# R602K.net
KiCad netlist of a schematic drawn in EAGLE
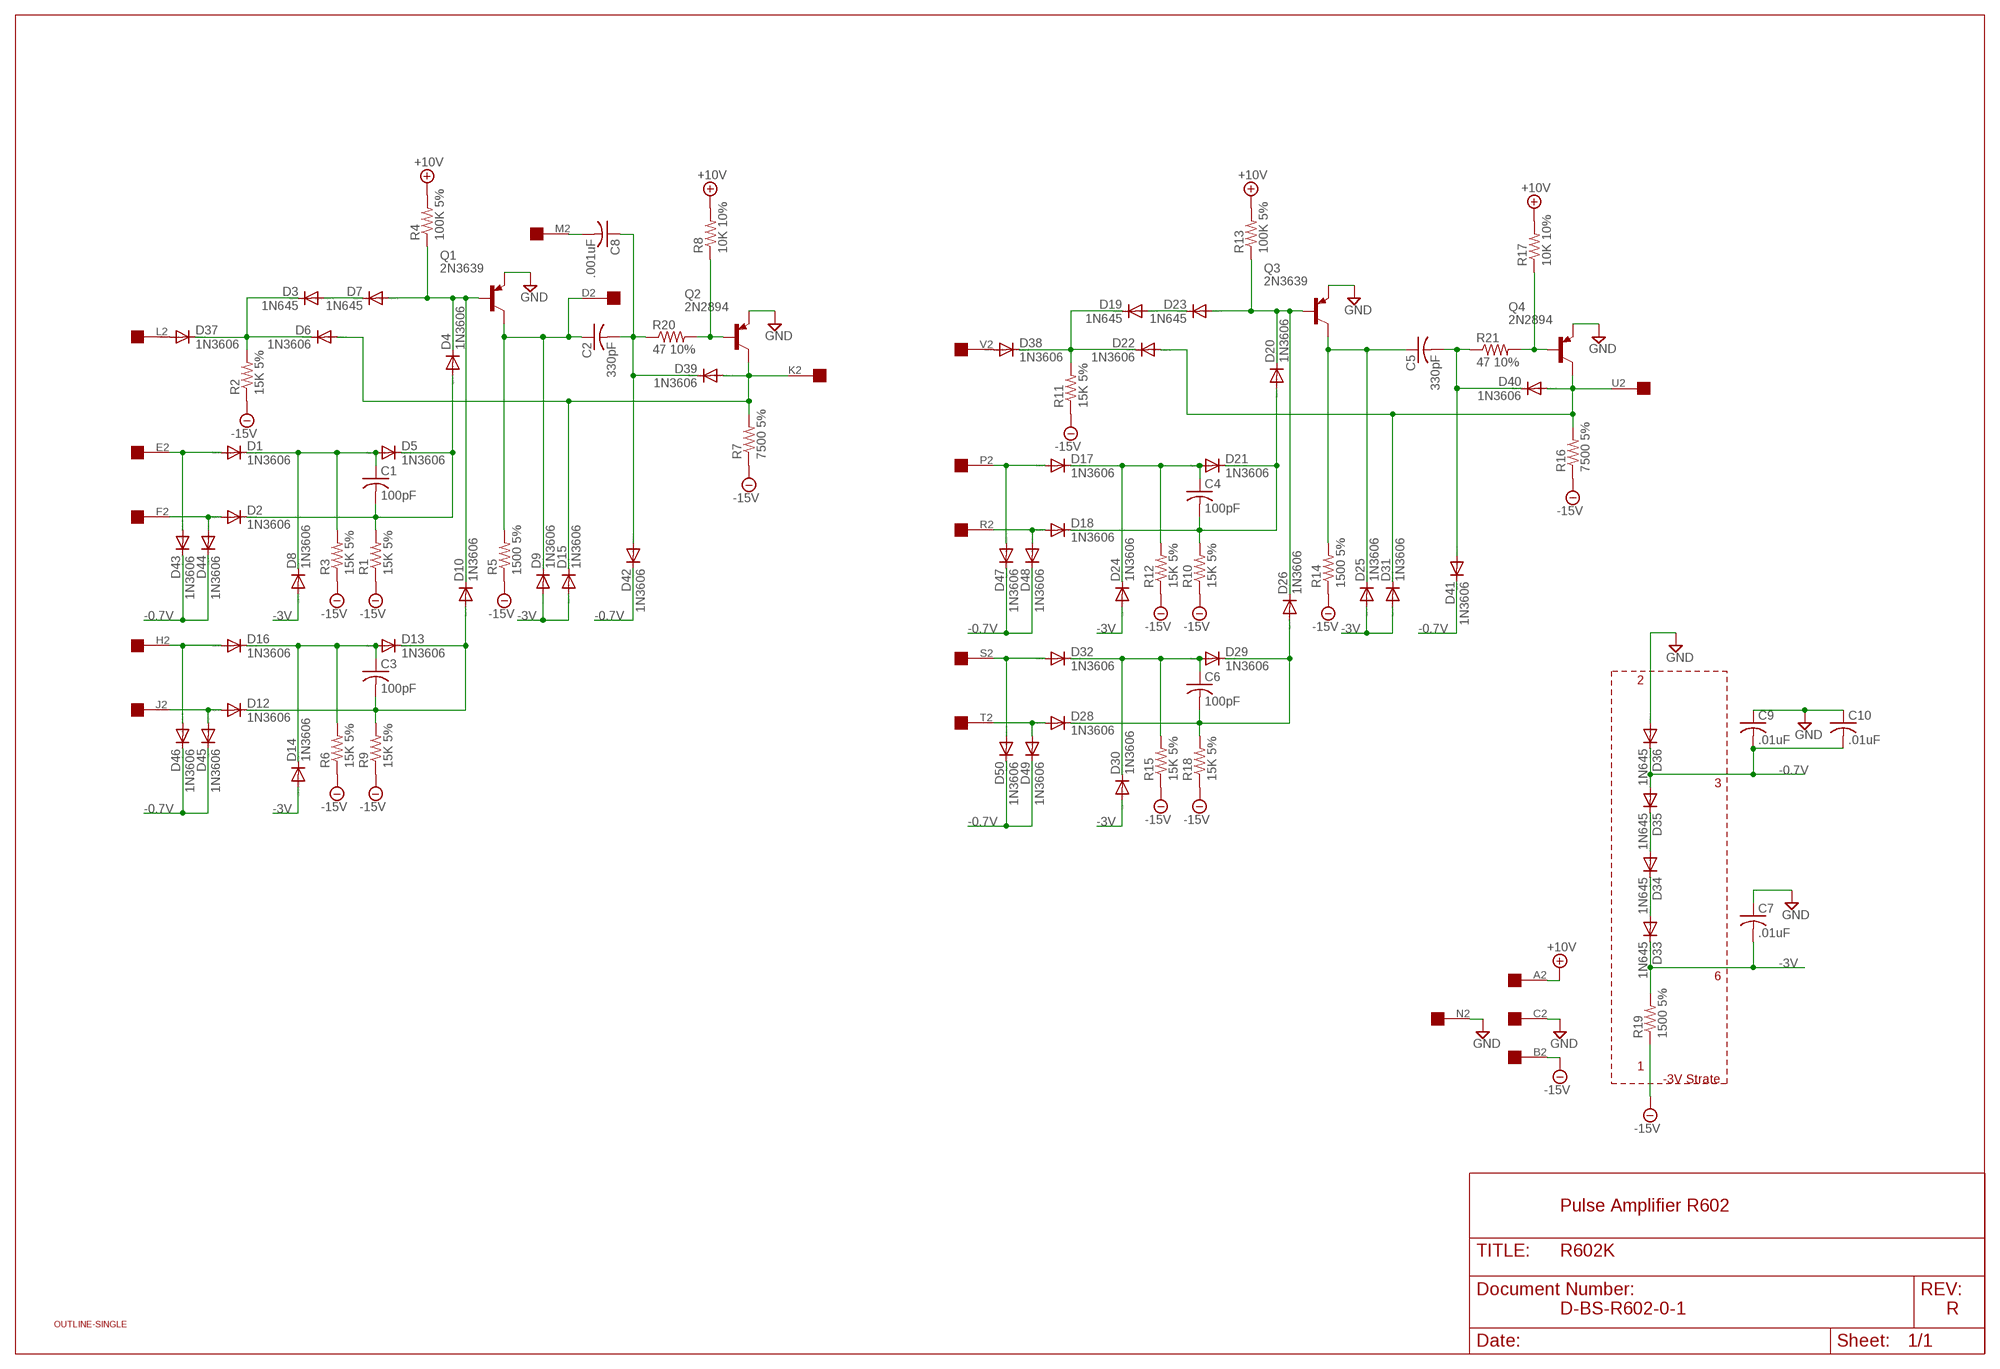
[diagram p0: schematic, sheet 1]

(export (version "E")
  (design (tool "Eeschema 10.0.6"))
  (components
    (comp (ref "C1")
      (value "100pF")
      (footprint "eagle-import:C050-025X075")
      (libsource (lib "eagle-import") (part "C-US050-025X075"))
    )
    (comp (ref "C2")
      (value "330pF")
      (footprint "eagle-import:C050-025X075")
      (libsource (lib "eagle-import") (part "C-US050-025X075"))
    )
    (comp (ref "C3")
      (value "100pF")
      (footprint "eagle-import:C050-025X075")
      (libsource (lib "eagle-import") (part "C-US050-025X075"))
    )
    (comp (ref "C4")
      (value "100pF")
      (footprint "eagle-import:C050-025X075")
      (libsource (lib "eagle-import") (part "C-US050-025X075"))
    )
    (comp (ref "C5")
      (value "330pF")
      (footprint "eagle-import:C050-025X075")
      (libsource (lib "eagle-import") (part "C-US050-025X075"))
    )
    (comp (ref "C6")
      (value "100pF")
      (footprint "eagle-import:C050-025X075")
      (libsource (lib "eagle-import") (part "C-US050-025X075"))
    )
    (comp (ref "C7")
      (value ".01uF")
      (footprint "eagle-import:C075-032X103")
      (libsource (lib "eagle-import") (part "C-US075-032X103"))
    )
    (comp (ref "C8")
      (value ".001uF")
      (footprint "eagle-import:C050-025X075")
      (libsource (lib "eagle-import") (part "C-US050-025X075"))
    )
    (comp (ref "C9")
      (value ".01uF")
      (footprint "eagle-import:C050-025X075")
      (libsource (lib "eagle-import") (part "C-US050-025X075"))
    )
    (comp (ref "C10")
      (value ".01uF")
      (footprint "eagle-import:C050-025X075")
      (libsource (lib "eagle-import") (part "C-US050-025X075"))
    )
    (comp (ref "D1")
      (value "1N3606")
      (footprint "eagle-import:DO35-10")
      (libsource (lib "eagle-import") (part "1N4148DO35-10"))
    )
    (comp (ref "D2")
      (value "1N3606")
      (footprint "eagle-import:DO35-10")
      (libsource (lib "eagle-import") (part "1N4148DO35-10"))
    )
    (comp (ref "D3")
      (value "1N645")
      (footprint "eagle-import:DO35-10")
      (libsource (lib "eagle-import") (part "1N4148DO35-10"))
    )
    (comp (ref "D4")
      (value "1N3606")
      (footprint "eagle-import:DO35-10")
      (libsource (lib "eagle-import") (part "1N4148DO35-10"))
    )
    (comp (ref "D5")
      (value "1N3606")
      (footprint "eagle-import:DO35-10")
      (libsource (lib "eagle-import") (part "1N4148DO35-10"))
    )
    (comp (ref "D6")
      (value "1N3606")
      (footprint "eagle-import:DO35-10")
      (libsource (lib "eagle-import") (part "1N4148DO35-10"))
    )
    (comp (ref "D7")
      (value "1N645")
      (footprint "eagle-import:DO35-10")
      (libsource (lib "eagle-import") (part "1N4148DO35-10"))
    )
    (comp (ref "D8")
      (value "1N3606")
      (footprint "eagle-import:DO35-10")
      (libsource (lib "eagle-import") (part "1N4148DO35-10"))
    )
    (comp (ref "D9")
      (value "1N3606")
      (footprint "eagle-import:DO35-10")
      (libsource (lib "eagle-import") (part "1N4148DO35-10"))
    )
    (comp (ref "D10")
      (value "1N3606")
      (footprint "eagle-import:DO35-10")
      (libsource (lib "eagle-import") (part "1N4148DO35-10"))
    )
    (comp (ref "D12")
      (value "1N3606")
      (footprint "eagle-import:DO35-10")
      (libsource (lib "eagle-import") (part "1N4148DO35-10"))
    )
    (comp (ref "D13")
      (value "1N3606")
      (footprint "eagle-import:DO35-10")
      (libsource (lib "eagle-import") (part "1N4148DO35-10"))
    )
    (comp (ref "D14")
      (value "1N3606")
      (footprint "eagle-import:DO35-10")
      (libsource (lib "eagle-import") (part "1N4148DO35-10"))
    )
    (comp (ref "D15")
      (value "1N3606")
      (footprint "eagle-import:DO35-10")
      (libsource (lib "eagle-import") (part "1N4148DO35-10"))
    )
    (comp (ref "D16")
      (value "1N3606")
      (footprint "eagle-import:DO35-10")
      (libsource (lib "eagle-import") (part "1N4148DO35-10"))
    )
    (comp (ref "D17")
      (value "1N3606")
      (footprint "eagle-import:DO35-10")
      (libsource (lib "eagle-import") (part "1N4148DO35-10"))
    )
    (comp (ref "D18")
      (value "1N3606")
      (footprint "eagle-import:DO35-10")
      (libsource (lib "eagle-import") (part "1N4148DO35-10"))
    )
    (comp (ref "D19")
      (value "1N645")
      (footprint "eagle-import:DO35-10")
      (libsource (lib "eagle-import") (part "1N4148DO35-10"))
    )
    (comp (ref "D20")
      (value "1N3606")
      (footprint "eagle-import:DO35-10")
      (libsource (lib "eagle-import") (part "1N4148DO35-10"))
    )
    (comp (ref "D21")
      (value "1N3606")
      (footprint "eagle-import:DO35-10")
      (libsource (lib "eagle-import") (part "1N4148DO35-10"))
    )
    (comp (ref "D22")
      (value "1N3606")
      (footprint "eagle-import:DO35-10")
      (libsource (lib "eagle-import") (part "1N4148DO35-10"))
    )
    (comp (ref "D23")
      (value "1N645")
      (footprint "eagle-import:DO35-10")
      (libsource (lib "eagle-import") (part "1N4148DO35-10"))
    )
    (comp (ref "D24")
      (value "1N3606")
      (footprint "eagle-import:DO35-10")
      (libsource (lib "eagle-import") (part "1N4148DO35-10"))
    )
    (comp (ref "D25")
      (value "1N3606")
      (footprint "eagle-import:DO35-10")
      (libsource (lib "eagle-import") (part "1N4148DO35-10"))
    )
    (comp (ref "D26")
      (value "1N3606")
      (footprint "eagle-import:DO35-10")
      (libsource (lib "eagle-import") (part "1N4148DO35-10"))
    )
    (comp (ref "D28")
      (value "1N3606")
      (footprint "eagle-import:DO35-10")
      (libsource (lib "eagle-import") (part "1N4148DO35-10"))
    )
    (comp (ref "D29")
      (value "1N3606")
      (footprint "eagle-import:DO35-10")
      (libsource (lib "eagle-import") (part "1N4148DO35-10"))
    )
    (comp (ref "D30")
      (value "1N3606")
      (footprint "eagle-import:DO35-10")
      (libsource (lib "eagle-import") (part "1N4148DO35-10"))
    )
    (comp (ref "D31")
      (value "1N3606")
      (footprint "eagle-import:DO35-10")
      (libsource (lib "eagle-import") (part "1N4148DO35-10"))
    )
    (comp (ref "D32")
      (value "1N3606")
      (footprint "eagle-import:DO35-10")
      (libsource (lib "eagle-import") (part "1N4148DO35-10"))
    )
    (comp (ref "D33")
      (value "1N645")
      (footprint "eagle-import:DO35-10")
      (libsource (lib "eagle-import") (part "1N4148DO35-10"))
    )
    (comp (ref "D34")
      (value "1N645")
      (footprint "eagle-import:DO35-10")
      (libsource (lib "eagle-import") (part "1N4148DO35-10"))
    )
    (comp (ref "D35")
      (value "1N645")
      (footprint "eagle-import:DO35-10")
      (libsource (lib "eagle-import") (part "1N4148DO35-10"))
    )
    (comp (ref "D36")
      (value "1N645")
      (footprint "eagle-import:DO35-10")
      (libsource (lib "eagle-import") (part "1N4148DO35-10"))
    )
    (comp (ref "D37")
      (value "1N3606")
      (footprint "eagle-import:DO35-10")
      (libsource (lib "eagle-import") (part "1N4148DO35-10"))
    )
    (comp (ref "D38")
      (value "1N3606")
      (footprint "eagle-import:DO35-10")
      (libsource (lib "eagle-import") (part "1N4148DO35-10"))
    )
    (comp (ref "D39")
      (value "1N3606")
      (footprint "eagle-import:DO35-10")
      (libsource (lib "eagle-import") (part "1N4148DO35-10"))
    )
    (comp (ref "D40")
      (value "1N3606")
      (footprint "eagle-import:DO35-10")
      (libsource (lib "eagle-import") (part "1N4148DO35-10"))
    )
    (comp (ref "D41")
      (value "1N3606")
      (footprint "eagle-import:DO35-10")
      (libsource (lib "eagle-import") (part "1N4148DO35-10"))
    )
    (comp (ref "D42")
      (value "1N3606")
      (footprint "eagle-import:DO35-10")
      (libsource (lib "eagle-import") (part "1N4148DO35-10"))
    )
    (comp (ref "D43")
      (value "1N3606")
      (footprint "eagle-import:DO35-10")
      (libsource (lib "eagle-import") (part "1N4148DO35-10"))
    )
    (comp (ref "D44")
      (value "1N3606")
      (footprint "eagle-import:DO35-10")
      (libsource (lib "eagle-import") (part "1N4148DO35-10"))
    )
    (comp (ref "D45")
      (value "1N3606")
      (footprint "eagle-import:DO35-10")
      (libsource (lib "eagle-import") (part "1N4148DO35-10"))
    )
    (comp (ref "D46")
      (value "1N3606")
      (footprint "eagle-import:DO35-10")
      (libsource (lib "eagle-import") (part "1N4148DO35-10"))
    )
    (comp (ref "D47")
      (value "1N3606")
      (footprint "eagle-import:DO35-10")
      (libsource (lib "eagle-import") (part "1N4148DO35-10"))
    )
    (comp (ref "D48")
      (value "1N3606")
      (footprint "eagle-import:DO35-10")
      (libsource (lib "eagle-import") (part "1N4148DO35-10"))
    )
    (comp (ref "D49")
      (value "1N3606")
      (footprint "eagle-import:DO35-10")
      (libsource (lib "eagle-import") (part "1N4148DO35-10"))
    )
    (comp (ref "D50")
      (value "1N3606")
      (footprint "eagle-import:DO35-10")
      (libsource (lib "eagle-import") (part "1N4148DO35-10"))
    )
    (comp (ref "Q1")
      (value "2N3639")
      (footprint "eagle-import:TO39")
      (libsource (lib "eagle-import") (part "2N2904"))
    )
    (comp (ref "Q2")
      (value "2N2894")
      (footprint "eagle-import:TO39")
      (libsource (lib "eagle-import") (part "2N2904"))
    )
    (comp (ref "Q3")
      (value "2N3639")
      (footprint "eagle-import:TO39")
      (libsource (lib "eagle-import") (part "2N2904"))
    )
    (comp (ref "Q4")
      (value "2N2894")
      (footprint "eagle-import:TO39")
      (libsource (lib "eagle-import") (part "2N2904"))
    )
    (comp (ref "R1")
      (value "15K 5%")
      (footprint "eagle-import:0207_10")
      (libsource (lib "eagle-import") (part "R-US_0207/10"))
    )
    (comp (ref "R2")
      (value "15K 5%")
      (footprint "eagle-import:0207_10")
      (libsource (lib "eagle-import") (part "R-US_0207/10"))
    )
    (comp (ref "R3")
      (value "15K 5%")
      (footprint "eagle-import:0207_10")
      (libsource (lib "eagle-import") (part "R-US_0207/10"))
    )
    (comp (ref "R4")
      (value "100K 5%")
      (footprint "eagle-import:0207_10")
      (libsource (lib "eagle-import") (part "R-US_0207/10"))
    )
    (comp (ref "R5")
      (value "1500 5%")
      (footprint "eagle-import:0207_10")
      (libsource (lib "eagle-import") (part "R-US_0207/10"))
    )
    (comp (ref "R6")
      (value "15K 5%")
      (footprint "eagle-import:0207_10")
      (libsource (lib "eagle-import") (part "R-US_0207/10"))
    )
    (comp (ref "R7")
      (value "7500 5%")
      (footprint "eagle-import:0207_10")
      (libsource (lib "eagle-import") (part "R-US_0207/10"))
    )
    (comp (ref "R8")
      (value "10K 10%")
      (footprint "eagle-import:0207_10")
      (libsource (lib "eagle-import") (part "R-US_0207/10"))
    )
    (comp (ref "R9")
      (value "15K 5%")
      (footprint "eagle-import:0207_10")
      (libsource (lib "eagle-import") (part "R-US_0207/10"))
    )
    (comp (ref "R10")
      (value "15K 5%")
      (footprint "eagle-import:0207_10")
      (libsource (lib "eagle-import") (part "R-US_0207/10"))
    )
    (comp (ref "R11")
      (value "15K 5%")
      (footprint "eagle-import:0207_10")
      (libsource (lib "eagle-import") (part "R-US_0207/10"))
    )
    (comp (ref "R12")
      (value "15K 5%")
      (footprint "eagle-import:0207_10")
      (libsource (lib "eagle-import") (part "R-US_0207/10"))
    )
    (comp (ref "R13")
      (value "100K 5%")
      (footprint "eagle-import:0207_10")
      (libsource (lib "eagle-import") (part "R-US_0207/10"))
    )
    (comp (ref "R14")
      (value "1500 5%")
      (footprint "eagle-import:0207_10")
      (libsource (lib "eagle-import") (part "R-US_0207/10"))
    )
    (comp (ref "R15")
      (value "15K 5%")
      (footprint "eagle-import:0207_10")
      (libsource (lib "eagle-import") (part "R-US_0207/10"))
    )
    (comp (ref "R16")
      (value "7500 5%")
      (footprint "eagle-import:0207_10")
      (libsource (lib "eagle-import") (part "R-US_0207/10"))
    )
    (comp (ref "R17")
      (value "10K 10%")
      (footprint "eagle-import:0207_10")
      (libsource (lib "eagle-import") (part "R-US_0207/10"))
    )
    (comp (ref "R18")
      (value "15K 5%")
      (footprint "eagle-import:0207_10")
      (libsource (lib "eagle-import") (part "R-US_0207/10"))
    )
    (comp (ref "R19")
      (value "1500 5%")
      (footprint "eagle-import:0207_10")
      (libsource (lib "eagle-import") (part "R-US_0207/10"))
    )
    (comp (ref "R20")
      (value "47 10%")
      (footprint "eagle-import:0207_10")
      (libsource (lib "eagle-import") (part "R-US_0207/10"))
    )
    (comp (ref "R21")
      (value "47 10%")
      (footprint "eagle-import:0207_10")
      (libsource (lib "eagle-import") (part "R-US_0207/10"))
    )
    (comp (ref "U$1")
      (value "OUTLINE-SINGLE")
      (footprint "eagle-import:SINGLE")
      (libsource (lib "eagle-import") (part "OUTLINE-SINGLE"))
    )
    (comp (ref "U$2")
      (value "EDGE-1")
      (footprint "eagle-import:EDGE-CON1")
      (libsource (lib "eagle-import") (part "EDGE-1"))
    )
  )
  (nets
    (net (code "1") (name "+10V") (class "Default")
      (node (ref "R13") (pin "2") (pinfunction "2_2") (pintype "passive"))
      (node (ref "R17") (pin "2") (pinfunction "2_2") (pintype "passive"))
      (node (ref "R4") (pin "2") (pinfunction "2_2") (pintype "passive"))
      (node (ref "R8") (pin "2") (pinfunction "2_2") (pintype "passive"))
      (node (ref "U$2") (pin "A2") (pinfunction "1_A2") (pintype "bidirectional"))
    )
    (net (code "2") (name "-15V") (class "Default")
      (node (ref "R1") (pin "1") (pinfunction "1_1") (pintype "passive"))
      (node (ref "R10") (pin "1") (pinfunction "1_1") (pintype "passive"))
      (node (ref "R11") (pin "1") (pinfunction "1_1") (pintype "passive"))
      (node (ref "R12") (pin "1") (pinfunction "1_1") (pintype "passive"))
      (node (ref "R14") (pin "1") (pinfunction "1_1") (pintype "passive"))
      (node (ref "R15") (pin "1") (pinfunction "1_1") (pintype "passive"))
      (node (ref "R16") (pin "1") (pinfunction "1_1") (pintype "passive"))
      (node (ref "R18") (pin "1") (pinfunction "1_1") (pintype "passive"))
      (node (ref "R19") (pin "1") (pinfunction "1_1") (pintype "passive"))
      (node (ref "R2") (pin "1") (pinfunction "1_1") (pintype "passive"))
      (node (ref "R3") (pin "1") (pinfunction "1_1") (pintype "passive"))
      (node (ref "R5") (pin "1") (pinfunction "1_1") (pintype "passive"))
      (node (ref "R6") (pin "1") (pinfunction "1_1") (pintype "passive"))
      (node (ref "R7") (pin "1") (pinfunction "1_1") (pintype "passive"))
      (node (ref "R9") (pin "1") (pinfunction "1_1") (pintype "passive"))
      (node (ref "U$2") (pin "B2") (pinfunction "1_B2") (pintype "bidirectional"))
    )
    (net (code "3") (name "/-0.7V") (class "Default")
      (node (ref "C10") (pin "2") (pinfunction "2_2") (pintype "passive"))
      (node (ref "C9") (pin "2") (pinfunction "2_2") (pintype "passive"))
      (node (ref "D35") (pin "A") (pinfunction "A_A") (pintype "passive"))
      (node (ref "D36") (pin "C") (pinfunction "C_C") (pintype "passive"))
      (node (ref "D41") (pin "C") (pinfunction "C_C") (pintype "passive"))
      (node (ref "D42") (pin "C") (pinfunction "C_C") (pintype "passive"))
      (node (ref "D43") (pin "C") (pinfunction "C_C") (pintype "passive"))
      (node (ref "D44") (pin "C") (pinfunction "C_C") (pintype "passive"))
      (node (ref "D45") (pin "C") (pinfunction "C_C") (pintype "passive"))
      (node (ref "D46") (pin "C") (pinfunction "C_C") (pintype "passive"))
      (node (ref "D47") (pin "C") (pinfunction "C_C") (pintype "passive"))
      (node (ref "D48") (pin "C") (pinfunction "C_C") (pintype "passive"))
      (node (ref "D49") (pin "C") (pinfunction "C_C") (pintype "passive"))
      (node (ref "D50") (pin "C") (pinfunction "C_C") (pintype "passive"))
    )
    (net (code "4") (name "/-3V") (class "Default")
      (node (ref "C7") (pin "2") (pinfunction "2_2") (pintype "passive"))
      (node (ref "D14") (pin "A") (pinfunction "A_A") (pintype "passive"))
      (node (ref "D15") (pin "A") (pinfunction "A_A") (pintype "passive"))
      (node (ref "D24") (pin "A") (pinfunction "A_A") (pintype "passive"))
      (node (ref "D25") (pin "A") (pinfunction "A_A") (pintype "passive"))
      (node (ref "D30") (pin "A") (pinfunction "A_A") (pintype "passive"))
      (node (ref "D31") (pin "A") (pinfunction "A_A") (pintype "passive"))
      (node (ref "D33") (pin "C") (pinfunction "C_C") (pintype "passive"))
      (node (ref "D8") (pin "A") (pinfunction "A_A") (pintype "passive"))
      (node (ref "D9") (pin "A") (pinfunction "A_A") (pintype "passive"))
      (node (ref "R19") (pin "2") (pinfunction "2_2") (pintype "passive"))
    )
    (net (code "5") (name "GND") (class "Default")
      (node (ref "C10") (pin "1") (pinfunction "1_1") (pintype "passive"))
      (node (ref "C7") (pin "1") (pinfunction "1_1") (pintype "passive"))
      (node (ref "C9") (pin "1") (pinfunction "1_1") (pintype "passive"))
      (node (ref "D36") (pin "A") (pinfunction "A_A") (pintype "passive"))
      (node (ref "Q1") (pin "1") (pinfunction "E_1") (pintype "passive"))
      (node (ref "Q2") (pin "1") (pinfunction "E_1") (pintype "passive"))
      (node (ref "Q3") (pin "1") (pinfunction "E_1") (pintype "passive"))
      (node (ref "Q4") (pin "1") (pinfunction "E_1") (pintype "passive"))
      (node (ref "U$2") (pin "C2") (pinfunction "1_C2") (pintype "bidirectional"))
      (node (ref "U$2") (pin "N2") (pinfunction "1_N2") (pintype "bidirectional"))
    )
    (net (code "6") (name "Net-(C1-Pad1)") (class "Default")
      (node (ref "C1") (pin "1") (pinfunction "1_1") (pintype "passive"))
      (node (ref "D1") (pin "C") (pinfunction "C_C") (pintype "passive"))
      (node (ref "D5") (pin "A") (pinfunction "A_A") (pintype "passive"))
      (node (ref "D8") (pin "C") (pinfunction "C_C") (pintype "passive"))
      (node (ref "R3") (pin "2") (pinfunction "2_2") (pintype "passive"))
    )
    (net (code "7") (name "Net-(C1-Pad2)") (class "Default")
      (node (ref "C1") (pin "2") (pinfunction "2_2") (pintype "passive"))
      (node (ref "D2") (pin "C") (pinfunction "C_C") (pintype "passive"))
      (node (ref "D4") (pin "A") (pinfunction "A_A") (pintype "passive"))
      (node (ref "D5") (pin "C") (pinfunction "C_C") (pintype "passive"))
      (node (ref "R1") (pin "2") (pinfunction "2_2") (pintype "passive"))
    )
    (net (code "8") (name "Net-(C2-Pad2)") (class "Default")
      (node (ref "C2") (pin "2") (pinfunction "2_2") (pintype "passive"))
      (node (ref "C8") (pin "1") (pinfunction "1_1") (pintype "passive"))
      (node (ref "D39") (pin "C") (pinfunction "C_C") (pintype "passive"))
      (node (ref "D42") (pin "A") (pinfunction "A_A") (pintype "passive"))
      (node (ref "R20") (pin "1") (pinfunction "1_1") (pintype "passive"))
    )
    (net (code "9") (name "Net-(C3-Pad1)") (class "Default")
      (node (ref "C3") (pin "1") (pinfunction "1_1") (pintype "passive"))
      (node (ref "D13") (pin "A") (pinfunction "A_A") (pintype "passive"))
      (node (ref "D14") (pin "C") (pinfunction "C_C") (pintype "passive"))
      (node (ref "D16") (pin "C") (pinfunction "C_C") (pintype "passive"))
      (node (ref "R6") (pin "2") (pinfunction "2_2") (pintype "passive"))
    )
    (net (code "10") (name "Net-(C3-Pad2)") (class "Default")
      (node (ref "C3") (pin "2") (pinfunction "2_2") (pintype "passive"))
      (node (ref "D10") (pin "A") (pinfunction "A_A") (pintype "passive"))
      (node (ref "D12") (pin "C") (pinfunction "C_C") (pintype "passive"))
      (node (ref "D13") (pin "C") (pinfunction "C_C") (pintype "passive"))
      (node (ref "R9") (pin "2") (pinfunction "2_2") (pintype "passive"))
    )
    (net (code "11") (name "Net-(C4-Pad1)") (class "Default")
      (node (ref "C4") (pin "1") (pinfunction "1_1") (pintype "passive"))
      (node (ref "D17") (pin "C") (pinfunction "C_C") (pintype "passive"))
      (node (ref "D21") (pin "A") (pinfunction "A_A") (pintype "passive"))
      (node (ref "D24") (pin "C") (pinfunction "C_C") (pintype "passive"))
      (node (ref "R12") (pin "2") (pinfunction "2_2") (pintype "passive"))
    )
    (net (code "12") (name "Net-(C4-Pad2)") (class "Default")
      (node (ref "C4") (pin "2") (pinfunction "2_2") (pintype "passive"))
      (node (ref "D18") (pin "C") (pinfunction "C_C") (pintype "passive"))
      (node (ref "D20") (pin "A") (pinfunction "A_A") (pintype "passive"))
      (node (ref "D21") (pin "C") (pinfunction "C_C") (pintype "passive"))
      (node (ref "R10") (pin "2") (pinfunction "2_2") (pintype "passive"))
    )
    (net (code "13") (name "Net-(C5-Pad2)") (class "Default")
      (node (ref "C5") (pin "2") (pinfunction "2_2") (pintype "passive"))
      (node (ref "D40") (pin "C") (pinfunction "C_C") (pintype "passive"))
      (node (ref "D41") (pin "A") (pinfunction "A_A") (pintype "passive"))
      (node (ref "R21") (pin "1") (pinfunction "1_1") (pintype "passive"))
    )
    (net (code "14") (name "Net-(C6-Pad1)") (class "Default")
      (node (ref "C6") (pin "1") (pinfunction "1_1") (pintype "passive"))
      (node (ref "D29") (pin "A") (pinfunction "A_A") (pintype "passive"))
      (node (ref "D30") (pin "C") (pinfunction "C_C") (pintype "passive"))
      (node (ref "D32") (pin "C") (pinfunction "C_C") (pintype "passive"))
      (node (ref "R15") (pin "2") (pinfunction "2_2") (pintype "passive"))
    )
    (net (code "15") (name "Net-(C6-Pad2)") (class "Default")
      (node (ref "C6") (pin "2") (pinfunction "2_2") (pintype "passive"))
      (node (ref "D26") (pin "A") (pinfunction "A_A") (pintype "passive"))
      (node (ref "D28") (pin "C") (pinfunction "C_C") (pintype "passive"))
      (node (ref "D29") (pin "C") (pinfunction "C_C") (pintype "passive"))
      (node (ref "R18") (pin "2") (pinfunction "2_2") (pintype "passive"))
    )
    (net (code "16") (name "Net-(D3-PadA)") (class "Default")
      (node (ref "D3") (pin "A") (pinfunction "A_A") (pintype "passive"))
      (node (ref "D7") (pin "C") (pinfunction "C_C") (pintype "passive"))
    )
    (net (code "17") (name "Net-(D3-PadC)") (class "Default")
      (node (ref "D3") (pin "C") (pinfunction "C_C") (pintype "passive"))
      (node (ref "D37") (pin "C") (pinfunction "C_C") (pintype "passive"))
      (node (ref "D6") (pin "C") (pinfunction "C_C") (pintype "passive"))
      (node (ref "R2") (pin "2") (pinfunction "2_2") (pintype "passive"))
    )
    (net (code "18") (name "Net-(D19-PadA)") (class "Default")
      (node (ref "D19") (pin "A") (pinfunction "A_A") (pintype "passive"))
      (node (ref "D23") (pin "C") (pinfunction "C_C") (pintype "passive"))
    )
    (net (code "19") (name "Net-(D19-PadC)") (class "Default")
      (node (ref "D19") (pin "C") (pinfunction "C_C") (pintype "passive"))
      (node (ref "D22") (pin "C") (pinfunction "C_C") (pintype "passive"))
      (node (ref "D38") (pin "C") (pinfunction "C_C") (pintype "passive"))
      (node (ref "R11") (pin "2") (pinfunction "2_2") (pintype "passive"))
    )
    (net (code "20") (name "Net-(D33-PadA)") (class "Default")
      (node (ref "D33") (pin "A") (pinfunction "A_A") (pintype "passive"))
      (node (ref "D34") (pin "C") (pinfunction "C_C") (pintype "passive"))
    )
    (net (code "21") (name "Net-(D34-PadA)") (class "Default")
      (node (ref "D34") (pin "A") (pinfunction "A_A") (pintype "passive"))
      (node (ref "D35") (pin "C") (pinfunction "C_C") (pintype "passive"))
    )
    (net (code "22") (name "Net-(Q1-B)") (class "Default")
      (node (ref "D10") (pin "C") (pinfunction "C_C") (pintype "passive"))
      (node (ref "D4") (pin "C") (pinfunction "C_C") (pintype "passive"))
      (node (ref "D7") (pin "A") (pinfunction "A_A") (pintype "passive"))
      (node (ref "Q1") (pin "2") (pinfunction "B_2") (pintype "passive"))
      (node (ref "R4") (pin "1") (pinfunction "1_1") (pintype "passive"))
    )
    (net (code "23") (name "Net-(Q1-C)") (class "Default")
      (node (ref "C2") (pin "1") (pinfunction "1_1") (pintype "passive"))
      (node (ref "D9") (pin "C") (pinfunction "C_C") (pintype "passive"))
      (node (ref "Q1") (pin "3") (pinfunction "C_3") (pintype "passive"))
      (node (ref "R5") (pin "2") (pinfunction "2_2") (pintype "passive"))
      (node (ref "U$2") (pin "D2") (pinfunction "1_D2") (pintype "bidirectional"))
    )
    (net (code "24") (name "Net-(Q2-B)") (class "Default")
      (node (ref "Q2") (pin "2") (pinfunction "B_2") (pintype "passive"))
      (node (ref "R20") (pin "2") (pinfunction "2_2") (pintype "passive"))
      (node (ref "R8") (pin "1") (pinfunction "1_1") (pintype "passive"))
    )
    (net (code "25") (name "Net-(Q2-C)") (class "Default")
      (node (ref "D15") (pin "C") (pinfunction "C_C") (pintype "passive"))
      (node (ref "D39") (pin "A") (pinfunction "A_A") (pintype "passive"))
      (node (ref "D6") (pin "A") (pinfunction "A_A") (pintype "passive"))
      (node (ref "Q2") (pin "3") (pinfunction "C_3") (pintype "passive"))
      (node (ref "R7") (pin "2") (pinfunction "2_2") (pintype "passive"))
      (node (ref "U$2") (pin "K2") (pinfunction "1_K2") (pintype "bidirectional"))
    )
    (net (code "26") (name "Net-(Q3-B)") (class "Default")
      (node (ref "D20") (pin "C") (pinfunction "C_C") (pintype "passive"))
      (node (ref "D23") (pin "A") (pinfunction "A_A") (pintype "passive"))
      (node (ref "D26") (pin "C") (pinfunction "C_C") (pintype "passive"))
      (node (ref "Q3") (pin "2") (pinfunction "B_2") (pintype "passive"))
      (node (ref "R13") (pin "1") (pinfunction "1_1") (pintype "passive"))
    )
    (net (code "27") (name "Net-(Q3-C)") (class "Default")
      (node (ref "C5") (pin "1") (pinfunction "1_1") (pintype "passive"))
      (node (ref "D25") (pin "C") (pinfunction "C_C") (pintype "passive"))
      (node (ref "Q3") (pin "3") (pinfunction "C_3") (pintype "passive"))
      (node (ref "R14") (pin "2") (pinfunction "2_2") (pintype "passive"))
    )
    (net (code "28") (name "Net-(Q4-B)") (class "Default")
      (node (ref "Q4") (pin "2") (pinfunction "B_2") (pintype "passive"))
      (node (ref "R17") (pin "1") (pinfunction "1_1") (pintype "passive"))
      (node (ref "R21") (pin "2") (pinfunction "2_2") (pintype "passive"))
    )
    (net (code "29") (name "Net-(Q4-C)") (class "Default")
      (node (ref "D22") (pin "A") (pinfunction "A_A") (pintype "passive"))
      (node (ref "D31") (pin "C") (pinfunction "C_C") (pintype "passive"))
      (node (ref "D40") (pin "A") (pinfunction "A_A") (pintype "passive"))
      (node (ref "Q4") (pin "3") (pinfunction "C_3") (pintype "passive"))
      (node (ref "R16") (pin "2") (pinfunction "2_2") (pintype "passive"))
      (node (ref "U$2") (pin "U2") (pinfunction "1_U2") (pintype "bidirectional"))
    )
    (net (code "30") (name "Net-(U$2E-1)") (class "Default")
      (node (ref "D1") (pin "A") (pinfunction "A_A") (pintype "passive"))
      (node (ref "D43") (pin "A") (pinfunction "A_A") (pintype "passive"))
      (node (ref "U$2") (pin "E2") (pinfunction "1_E2") (pintype "bidirectional"))
    )
    (net (code "31") (name "Net-(U$2F-1)") (class "Default")
      (node (ref "D2") (pin "A") (pinfunction "A_A") (pintype "passive"))
      (node (ref "D44") (pin "A") (pinfunction "A_A") (pintype "passive"))
      (node (ref "U$2") (pin "F2") (pinfunction "1_F2") (pintype "bidirectional"))
    )
    (net (code "32") (name "Net-(U$2G-1)") (class "Default")
      (node (ref "D16") (pin "A") (pinfunction "A_A") (pintype "passive"))
      (node (ref "D46") (pin "A") (pinfunction "A_A") (pintype "passive"))
      (node (ref "U$2") (pin "H2") (pinfunction "1_H2") (pintype "bidirectional"))
    )
    (net (code "33") (name "Net-(U$2H-1)") (class "Default")
      (node (ref "D12") (pin "A") (pinfunction "A_A") (pintype "passive"))
      (node (ref "D45") (pin "A") (pinfunction "A_A") (pintype "passive"))
      (node (ref "U$2") (pin "J2") (pinfunction "1_J2") (pintype "bidirectional"))
    )
    (net (code "34") (name "Net-(U$2J-1)") (class "Default")
      (node (ref "D37") (pin "A") (pinfunction "A_A") (pintype "passive"))
      (node (ref "U$2") (pin "L2") (pinfunction "1_L2") (pintype "bidirectional"))
    )
    (net (code "35") (name "Net-(U$2K-1)") (class "Default")
      (node (ref "C8") (pin "2") (pinfunction "2_2") (pintype "passive"))
      (node (ref "U$2") (pin "M2") (pinfunction "1_M2") (pintype "bidirectional"))
    )
    (net (code "36") (name "Net-(U$2M-1)") (class "Default")
      (node (ref "D17") (pin "A") (pinfunction "A_A") (pintype "passive"))
      (node (ref "D47") (pin "A") (pinfunction "A_A") (pintype "passive"))
      (node (ref "U$2") (pin "P2") (pinfunction "1_P2") (pintype "bidirectional"))
    )
    (net (code "37") (name "Net-(U$2N-1)") (class "Default")
      (node (ref "D18") (pin "A") (pinfunction "A_A") (pintype "passive"))
      (node (ref "D48") (pin "A") (pinfunction "A_A") (pintype "passive"))
      (node (ref "U$2") (pin "R2") (pinfunction "1_R2") (pintype "bidirectional"))
    )
    (net (code "38") (name "Net-(U$2O-1)") (class "Default")
      (node (ref "D32") (pin "A") (pinfunction "A_A") (pintype "passive"))
      (node (ref "D50") (pin "A") (pinfunction "A_A") (pintype "passive"))
      (node (ref "U$2") (pin "S2") (pinfunction "1_S2") (pintype "bidirectional"))
    )
    (net (code "39") (name "Net-(U$2P-1)") (class "Default")
      (node (ref "D28") (pin "A") (pinfunction "A_A") (pintype "passive"))
      (node (ref "D49") (pin "A") (pinfunction "A_A") (pintype "passive"))
      (node (ref "U$2") (pin "T2") (pinfunction "1_T2") (pintype "bidirectional"))
    )
    (net (code "40") (name "Net-(U$2R-1)") (class "Default")
      (node (ref "D38") (pin "A") (pinfunction "A_A") (pintype "passive"))
      (node (ref "U$2") (pin "V2") (pinfunction "1_V2") (pintype "bidirectional"))
    )
  )
)
